# Tray2_Power_RedundantReg.net
KiCad netlist of a schematic drawn in Altium Designer
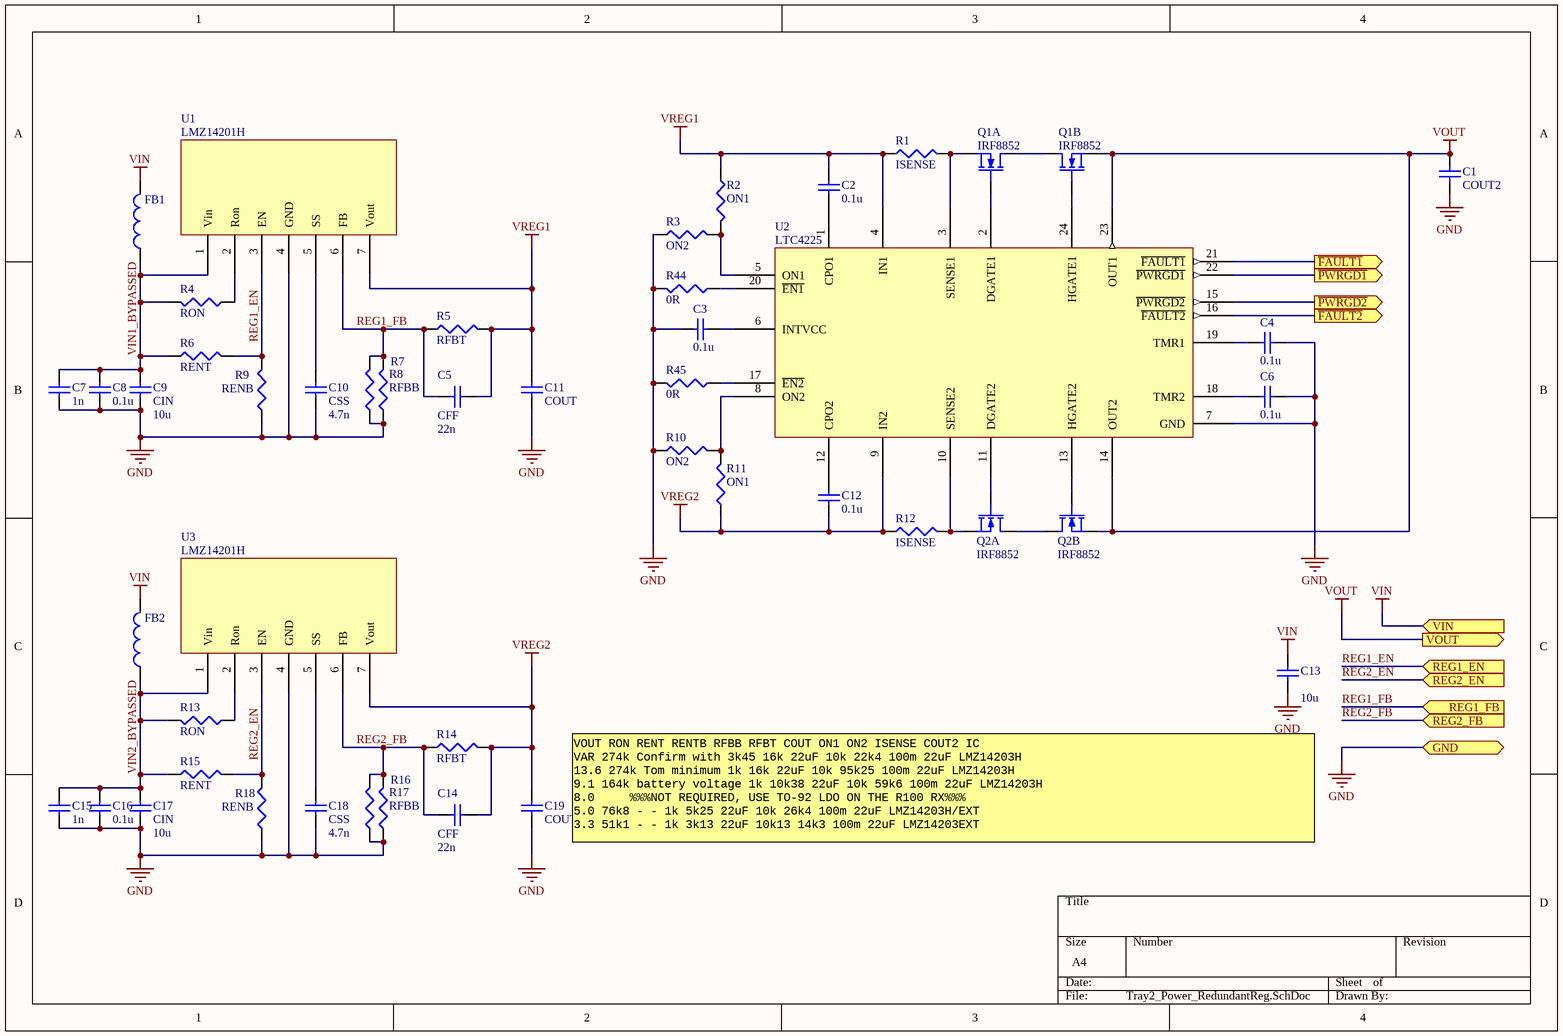
[diagram p0: Tray2_Power_RedundantReg.SchDoc]

(export (version "E")
  (design (tool "Eeschema 10.0.6"))
  (components
    (comp (ref "C1")
      (value "COUT2")
      (footprint "R1210M")
      (description "Capacitor")
      (fields (field (name "PUBLISHER") "Altium Limited"))
      (libsource (lib "Miscellaneous Devices") (part "Cap"))
    )
    (comp (ref "C2")
      (value "0.1u")
      (footprint "R0805M")
      (description "Capacitor")
      (fields (field (name "PUBLISHER") "Altium Limited"))
      (libsource (lib "Miscellaneous Devices") (part "Cap"))
    )
    (comp (ref "C3")
      (value "0.1u")
      (footprint "R0805M")
      (description "Capacitor")
      (fields (field (name "PUBLISHER") "Altium Limited"))
      (libsource (lib "Miscellaneous Devices") (part "Cap"))
    )
    (comp (ref "C4")
      (value "0.1u")
      (footprint "R0805M")
      (description "Capacitor")
      (fields (field (name "PUBLISHER") "Altium Limited"))
      (libsource (lib "Miscellaneous Devices") (part "Cap"))
    )
    (comp (ref "C5")
      (value "CFF")
      (footprint "R0805M")
      (description "Capacitor")
      (fields (field (name "ALTIUM_VALUE") "22n") (field (name "PUBLISHER") "Altium Limited"))
      (libsource (lib "Miscellaneous Devices") (part "Cap"))
    )
    (comp (ref "C6")
      (value "0.1u")
      (footprint "R0805M")
      (description "Capacitor")
      (fields (field (name "PUBLISHER") "Altium Limited"))
      (libsource (lib "Miscellaneous Devices") (part "Cap"))
    )
    (comp (ref "C7")
      (value "1n")
      (footprint "R0805M")
      (description "Capacitor")
      (fields (field (name "Comment") "CIN") (field (name "PUBLISHER") "Altium Limited"))
      (libsource (lib "Miscellaneous Devices") (part "Cap"))
    )
    (comp (ref "C8")
      (value "0.1u")
      (footprint "R0805M")
      (description "Capacitor")
      (fields (field (name "Comment") "CIN") (field (name "PUBLISHER") "Altium Limited"))
      (libsource (lib "Miscellaneous Devices") (part "Cap"))
    )
    (comp (ref "C9")
      (value "CIN")
      (footprint "R1210M")
      (description "Capacitor")
      (fields (field (name "ALTIUM_VALUE") "10u") (field (name "PUBLISHER") "Altium Limited"))
      (libsource (lib "Miscellaneous Devices") (part "Cap"))
    )
    (comp (ref "C10")
      (value "CSS")
      (footprint "R0805M")
      (description "Capacitor")
      (fields (field (name "ALTIUM_VALUE") "4.7n") (field (name "PUBLISHER") "Altium Limited"))
      (libsource (lib "Miscellaneous Devices") (part "Cap"))
    )
    (comp (ref "C11")
      (value "COUT")
      (footprint "R1210M")
      (description "Capacitor")
      (fields (field (name "PUBLISHER") "Altium Limited"))
      (libsource (lib "Miscellaneous Devices") (part "Cap"))
    )
    (comp (ref "C12")
      (value "0.1u")
      (footprint "R0805M")
      (description "Capacitor")
      (fields (field (name "PUBLISHER") "Altium Limited"))
      (libsource (lib "Miscellaneous Devices") (part "Cap"))
    )
    (comp (ref "C13")
      (value "10u")
      (footprint "R1210M")
      (description "Capacitor")
      (fields (field (name "PUBLISHER") "Altium Limited"))
      (libsource (lib "Miscellaneous Devices") (part "Cap"))
    )
    (comp (ref "C14")
      (value "CFF")
      (footprint "R0805M")
      (description "Capacitor")
      (fields (field (name "ALTIUM_VALUE") "22n") (field (name "PUBLISHER") "Altium Limited"))
      (libsource (lib "Miscellaneous Devices") (part "Cap"))
    )
    (comp (ref "C15")
      (value "1n")
      (footprint "R0805M")
      (description "Capacitor")
      (fields (field (name "Comment") "CIN") (field (name "PUBLISHER") "Altium Limited"))
      (libsource (lib "Miscellaneous Devices") (part "Cap"))
    )
    (comp (ref "C16")
      (value "0.1u")
      (footprint "R0805M")
      (description "Capacitor")
      (fields (field (name "Comment") "CIN") (field (name "PUBLISHER") "Altium Limited"))
      (libsource (lib "Miscellaneous Devices") (part "Cap"))
    )
    (comp (ref "C17")
      (value "CIN")
      (footprint "R1210M")
      (description "Capacitor")
      (fields (field (name "ALTIUM_VALUE") "10u") (field (name "PUBLISHER") "Altium Limited"))
      (libsource (lib "Miscellaneous Devices") (part "Cap"))
    )
    (comp (ref "C18")
      (value "CSS")
      (footprint "R0805M")
      (description "Capacitor")
      (fields (field (name "ALTIUM_VALUE") "4.7n") (field (name "PUBLISHER") "Altium Limited"))
      (libsource (lib "Miscellaneous Devices") (part "Cap"))
    )
    (comp (ref "C19")
      (value "COUT")
      (footprint "R1210M")
      (description "Capacitor")
      (fields (field (name "PUBLISHER") "Altium Limited"))
      (libsource (lib "Miscellaneous Devices") (part "Cap"))
    )
    (comp (ref "FB1")
      (value "~")
      (footprint "R0805M")
      (description "Inductor")
      (fields (field (name "PUBLISHER") "Altium Limited"))
      (libsource (lib "Miscellaneous Devices") (part "Inductor"))
    )
    (comp (ref "FB2")
      (value "~")
      (footprint "R0805M")
      (description "Inductor")
      (fields (field (name "PUBLISHER") "Altium Limited"))
      (libsource (lib "Miscellaneous Devices") (part "Inductor"))
    )
    (comp (ref "Q1")
      (value "IRF8852")
      (footprint "TSSOP8")
      (description "N-Channel MOSFET")
      (fields (field (name "PUBLISHER") "Altium Limited"))
      (libsource (lib "SchLib") (part "IRF8852"))
    )
    (comp (ref "Q2")
      (value "IRF8852")
      (footprint "TSSOP8")
      (description "N-Channel MOSFET")
      (fields (field (name "PUBLISHER") "Altium Limited"))
      (libsource (lib "SchLib") (part "IRF8852"))
    )
    (comp (ref "R1")
      (value "ISENSE")
      (footprint "R0805M")
      (description "Resistor")
      (fields (field (name "PUBLISHER") "Altium Limited"))
      (libsource (lib "Miscellaneous Devices") (part "Res3"))
    )
    (comp (ref "R2")
      (value "ON1")
      (footprint "R0805M")
      (description "Resistor")
      (fields (field (name "PUBLISHER") "Altium Limited"))
      (libsource (lib "Miscellaneous Devices") (part "Res3"))
    )
    (comp (ref "R3")
      (value "ON2")
      (footprint "R0805M")
      (description "Resistor")
      (fields (field (name "PUBLISHER") "Altium Limited"))
      (libsource (lib "Miscellaneous Devices") (part "Res3"))
    )
    (comp (ref "R4")
      (value "RON")
      (footprint "R0805M")
      (description "Resistor")
      (fields (field (name "PUBLISHER") "Altium Limited"))
      (libsource (lib "Miscellaneous Devices") (part "Res3"))
    )
    (comp (ref "R5")
      (value "RFBT")
      (footprint "R0805M")
      (description "Resistor")
      (fields (field (name "PUBLISHER") "Altium Limited"))
      (libsource (lib "Miscellaneous Devices") (part "Res3"))
    )
    (comp (ref "R6")
      (value "RENT")
      (footprint "R0805M")
      (description "Resistor")
      (fields (field (name "PUBLISHER") "Altium Limited"))
      (libsource (lib "Miscellaneous Devices") (part "Res3"))
    )
    (comp (ref "R7")
      (value "RFBB")
      (footprint "R0805M")
      (description "Resistor")
      (fields (field (name "PUBLISHER") "Altium Limited"))
      (libsource (lib "Miscellaneous Devices") (part "Res3"))
    )
    (comp (ref "R8")
      (value "RFBB")
      (footprint "R0805M")
      (description "Resistor")
      (fields (field (name "PUBLISHER") "Altium Limited"))
      (libsource (lib "Miscellaneous Devices") (part "Res3"))
    )
    (comp (ref "R9")
      (value "RENB")
      (footprint "R0805M")
      (description "Resistor")
      (fields (field (name "PUBLISHER") "Altium Limited"))
      (libsource (lib "Miscellaneous Devices") (part "Res3"))
    )
    (comp (ref "R10")
      (value "ON2")
      (footprint "R0805M")
      (description "Resistor")
      (fields (field (name "PUBLISHER") "Altium Limited"))
      (libsource (lib "Miscellaneous Devices") (part "Res3"))
    )
    (comp (ref "R11")
      (value "ON1")
      (footprint "R0805M")
      (description "Resistor")
      (fields (field (name "PUBLISHER") "Altium Limited"))
      (libsource (lib "Miscellaneous Devices") (part "Res3"))
    )
    (comp (ref "R12")
      (value "ISENSE")
      (footprint "R0805M")
      (description "Resistor")
      (fields (field (name "PUBLISHER") "Altium Limited"))
      (libsource (lib "Miscellaneous Devices") (part "Res3"))
    )
    (comp (ref "R13")
      (value "RON")
      (footprint "R0805M")
      (description "Resistor")
      (fields (field (name "PUBLISHER") "Altium Limited"))
      (libsource (lib "Miscellaneous Devices") (part "Res3"))
    )
    (comp (ref "R14")
      (value "RFBT")
      (footprint "R0805M")
      (description "Resistor")
      (fields (field (name "PUBLISHER") "Altium Limited"))
      (libsource (lib "Miscellaneous Devices") (part "Res3"))
    )
    (comp (ref "R15")
      (value "RENT")
      (footprint "R0805M")
      (description "Resistor")
      (fields (field (name "PUBLISHER") "Altium Limited"))
      (libsource (lib "Miscellaneous Devices") (part "Res3"))
    )
    (comp (ref "R16")
      (value "RFBB")
      (footprint "R0805M")
      (description "Resistor")
      (fields (field (name "PUBLISHER") "Altium Limited"))
      (libsource (lib "Miscellaneous Devices") (part "Res3"))
    )
    (comp (ref "R17")
      (value "RFBB")
      (footprint "R0805M")
      (description "Resistor")
      (fields (field (name "PUBLISHER") "Altium Limited"))
      (libsource (lib "Miscellaneous Devices") (part "Res3"))
    )
    (comp (ref "R18")
      (value "RENB")
      (footprint "R0805M")
      (description "Resistor")
      (fields (field (name "PUBLISHER") "Altium Limited"))
      (libsource (lib "Miscellaneous Devices") (part "Res3"))
    )
    (comp (ref "R44")
      (value "0R")
      (footprint "R0805M")
      (description "Resistor")
      (fields (field (name "PUBLISHER") "Altium Limited"))
      (libsource (lib "Miscellaneous Devices") (part "Res3"))
    )
    (comp (ref "R45")
      (value "0R")
      (footprint "R0805M")
      (description "Resistor")
      (fields (field (name "PUBLISHER") "Altium Limited"))
      (libsource (lib "Miscellaneous Devices") (part "Res3"))
    )
    (comp (ref "U1")
      (value "LMZ14201H")
      (footprint "TO-PMOD-7")
      (description "1A SIMPLE SWITCHER® Power Module for High Output  Voltage")
      (libsource (lib "SchLib") (part "LMZ14201H"))
    )
    (comp (ref "U2")
      (value "LTC4225")
      (footprint "SSOP24")
      (description "Dual Ideal Diode and  Hot Swap Controller")
      (libsource (lib "SchLib") (part "LTC4225"))
    )
    (comp (ref "U3")
      (value "LMZ14201H")
      (footprint "TO-PMOD-7")
      (description "1A SIMPLE SWITCHER® Power Module for High Output  Voltage")
      (libsource (lib "SchLib") (part "LMZ14201H"))
    )
  )
  (nets
    (net (code "1") (name "/REG1_EN") (class "Default")
      (node (ref "R6") (pin "2") (pinfunction "2_2") (pintype "passive"))
      (node (ref "R9") (pin "1") (pinfunction "1_1") (pintype "passive"))
      (node (ref "U1") (pin "3") (pinfunction "EN_3") (pintype "passive"))
    )
    (net (code "2") (name "/REG1_FB") (class "Default")
      (node (ref "C5") (pin "1") (pinfunction "1_1") (pintype "passive"))
      (node (ref "R5") (pin "1") (pinfunction "1_1") (pintype "passive"))
      (node (ref "R7") (pin "2") (pinfunction "2_2") (pintype "passive"))
      (node (ref "R8") (pin "2") (pinfunction "2_2") (pintype "passive"))
      (node (ref "U1") (pin "6") (pinfunction "FB_6") (pintype "passive"))
    )
    (net (code "3") (name "/REG2_EN") (class "Default")
      (node (ref "R15") (pin "2") (pinfunction "2_2") (pintype "passive"))
      (node (ref "R18") (pin "1") (pinfunction "1_1") (pintype "passive"))
      (node (ref "U3") (pin "3") (pinfunction "EN_3") (pintype "passive"))
    )
    (net (code "4") (name "/REG2_FB") (class "Default")
      (node (ref "C14") (pin "1") (pinfunction "1_1") (pintype "passive"))
      (node (ref "R14") (pin "1") (pinfunction "1_1") (pintype "passive"))
      (node (ref "R16") (pin "2") (pinfunction "2_2") (pintype "passive"))
      (node (ref "R17") (pin "2") (pinfunction "2_2") (pintype "passive"))
      (node (ref "U3") (pin "6") (pinfunction "FB_6") (pintype "passive"))
    )
    (net (code "5") (name "/VIN1_BYPASSED") (class "Default")
      (node (ref "C7") (pin "2") (pinfunction "2_2") (pintype "passive"))
      (node (ref "C8") (pin "2") (pinfunction "2_2") (pintype "passive"))
      (node (ref "C9") (pin "1") (pinfunction "1_1") (pintype "passive"))
      (node (ref "FB1") (pin "1") (pinfunction "1_1") (pintype "passive"))
      (node (ref "R4") (pin "2") (pinfunction "2_2") (pintype "passive"))
      (node (ref "R6") (pin "1") (pinfunction "1_1") (pintype "passive"))
      (node (ref "U1") (pin "1") (pinfunction "Vin_1") (pintype "passive"))
    )
    (net (code "6") (name "/VIN2_BYPASSED") (class "Default")
      (node (ref "C15") (pin "2") (pinfunction "2_2") (pintype "passive"))
      (node (ref "C16") (pin "2") (pinfunction "2_2") (pintype "passive"))
      (node (ref "C17") (pin "1") (pinfunction "1_1") (pintype "passive"))
      (node (ref "FB2") (pin "1") (pinfunction "1_1") (pintype "passive"))
      (node (ref "R13") (pin "2") (pinfunction "2_2") (pintype "passive"))
      (node (ref "R15") (pin "1") (pinfunction "1_1") (pintype "passive"))
      (node (ref "U3") (pin "1") (pinfunction "Vin_1") (pintype "passive"))
    )
    (net (code "7") (name "/~{FAULT1}") (class "Default")
      (node (ref "U2") (pin "21") (pinfunction "~{FAULT1}_21") (pintype "output"))
    )
    (net (code "8") (name "/~{FAULT2}") (class "Default")
      (node (ref "U2") (pin "16") (pinfunction "~{FAULT2}_16") (pintype "output"))
    )
    (net (code "9") (name "/~{PWRGD1}") (class "Default")
      (node (ref "U2") (pin "22") (pinfunction "~{PWRGD1}_22") (pintype "output"))
    )
    (net (code "10") (name "/~{PWRGD2}") (class "Default")
      (node (ref "U2") (pin "15") (pinfunction "~{PWRGD2}_15") (pintype "output"))
    )
    (net (code "11") (name "GND") (class "Default")
      (node (ref "C1") (pin "1") (pinfunction "1_1") (pintype "passive"))
      (node (ref "C10") (pin "2") (pinfunction "2_2") (pintype "passive"))
      (node (ref "C11") (pin "1") (pinfunction "1_1") (pintype "passive"))
      (node (ref "C13") (pin "2") (pinfunction "2_2") (pintype "passive"))
      (node (ref "C15") (pin "1") (pinfunction "1_1") (pintype "passive"))
      (node (ref "C16") (pin "1") (pinfunction "1_1") (pintype "passive"))
      (node (ref "C17") (pin "2") (pinfunction "2_2") (pintype "passive"))
      (node (ref "C18") (pin "2") (pinfunction "2_2") (pintype "passive"))
      (node (ref "C19") (pin "1") (pinfunction "1_1") (pintype "passive"))
      (node (ref "C3") (pin "2") (pinfunction "2_2") (pintype "passive"))
      (node (ref "C4") (pin "1") (pinfunction "1_1") (pintype "passive"))
      (node (ref "C6") (pin "1") (pinfunction "1_1") (pintype "passive"))
      (node (ref "C7") (pin "1") (pinfunction "1_1") (pintype "passive"))
      (node (ref "C8") (pin "1") (pinfunction "1_1") (pintype "passive"))
      (node (ref "C9") (pin "2") (pinfunction "2_2") (pintype "passive"))
      (node (ref "R10") (pin "1") (pinfunction "1_1") (pintype "passive"))
      (node (ref "R16") (pin "1") (pinfunction "1_1") (pintype "passive"))
      (node (ref "R17") (pin "1") (pinfunction "1_1") (pintype "passive"))
      (node (ref "R18") (pin "2") (pinfunction "2_2") (pintype "passive"))
      (node (ref "R3") (pin "1") (pinfunction "1_1") (pintype "passive"))
      (node (ref "R44") (pin "2") (pinfunction "2_2") (pintype "passive"))
      (node (ref "R45") (pin "2") (pinfunction "2_2") (pintype "passive"))
      (node (ref "R7") (pin "1") (pinfunction "1_1") (pintype "passive"))
      (node (ref "R8") (pin "1") (pinfunction "1_1") (pintype "passive"))
      (node (ref "R9") (pin "2") (pinfunction "2_2") (pintype "passive"))
      (node (ref "U1") (pin "4") (pinfunction "GND_4") (pintype "passive"))
      (node (ref "U2") (pin "7") (pinfunction "GND_7") (pintype "passive"))
      (node (ref "U3") (pin "4") (pinfunction "GND_4") (pintype "passive"))
    )
    (net (code "12") (name "Net-(Q1A-D)") (class "Default")
      (node (ref "Q1") (pin "D1") (pinfunction "D_D1") (pintype "passive"))
      (node (ref "Q1") (pin "D2") (pinfunction "D_D2") (pintype "passive"))
    )
    (net (code "13") (name "Net-(Q1A-G)") (class "Default")
      (node (ref "Q1") (pin "G1") (pinfunction "G_G1") (pintype "passive"))
      (node (ref "U2") (pin "2") (pinfunction "DGATE1_2") (pintype "passive"))
    )
    (net (code "14") (name "Net-(Q1A-S)") (class "Default")
      (node (ref "Q1") (pin "S1") (pinfunction "S_S1") (pintype "passive"))
      (node (ref "R1") (pin "2") (pinfunction "2_2") (pintype "passive"))
      (node (ref "U2") (pin "3") (pinfunction "SENSE1_3") (pintype "passive"))
    )
    (net (code "15") (name "Net-(Q1B-G)") (class "Default")
      (node (ref "Q1") (pin "G2") (pinfunction "G_G2") (pintype "passive"))
      (node (ref "U2") (pin "24") (pinfunction "HGATE1_24") (pintype "passive"))
    )
    (net (code "16") (name "Net-(Q2A-D)") (class "Default")
      (node (ref "Q2") (pin "D1") (pinfunction "D_D1") (pintype "passive"))
      (node (ref "Q2") (pin "D2") (pinfunction "D_D2") (pintype "passive"))
    )
    (net (code "17") (name "Net-(Q2A-G)") (class "Default")
      (node (ref "Q2") (pin "G1") (pinfunction "G_G1") (pintype "passive"))
      (node (ref "U2") (pin "11") (pinfunction "DGATE2_11") (pintype "passive"))
    )
    (net (code "18") (name "Net-(Q2A-S)") (class "Default")
      (node (ref "Q2") (pin "S1") (pinfunction "S_S1") (pintype "passive"))
      (node (ref "R12") (pin "2") (pinfunction "2_2") (pintype "passive"))
      (node (ref "U2") (pin "10") (pinfunction "SENSE2_10") (pintype "passive"))
    )
    (net (code "19") (name "Net-(Q2B-G)") (class "Default")
      (node (ref "Q2") (pin "G2") (pinfunction "G_G2") (pintype "passive"))
      (node (ref "U2") (pin "13") (pinfunction "HGATE2_13") (pintype "passive"))
    )
    (net (code "20") (name "Net-(U1-Ron)") (class "Default")
      (node (ref "R4") (pin "1") (pinfunction "1_1") (pintype "passive"))
      (node (ref "U1") (pin "2") (pinfunction "Ron_2") (pintype "passive"))
    )
    (net (code "21") (name "Net-(U1-SS)") (class "Default")
      (node (ref "C10") (pin "1") (pinfunction "1_1") (pintype "passive"))
      (node (ref "U1") (pin "5") (pinfunction "SS_5") (pintype "passive"))
    )
    (net (code "22") (name "Net-(U2-CPO1)") (class "Default")
      (node (ref "C2") (pin "2") (pinfunction "2_2") (pintype "passive"))
      (node (ref "U2") (pin "1") (pinfunction "CPO1_1") (pintype "passive"))
    )
    (net (code "23") (name "Net-(U2-CPO2)") (class "Default")
      (node (ref "C12") (pin "1") (pinfunction "1_1") (pintype "passive"))
      (node (ref "U2") (pin "12") (pinfunction "CPO2_12") (pintype "passive"))
    )
    (net (code "24") (name "Net-(U2-INTVCC)") (class "Default")
      (node (ref "C3") (pin "1") (pinfunction "1_1") (pintype "passive"))
      (node (ref "U2") (pin "6") (pinfunction "INTVCC_6") (pintype "passive"))
    )
    (net (code "25") (name "Net-(U2-ON1)") (class "Default")
      (node (ref "R2") (pin "2") (pinfunction "2_2") (pintype "passive"))
      (node (ref "R3") (pin "2") (pinfunction "2_2") (pintype "passive"))
      (node (ref "U2") (pin "5") (pinfunction "ON1_5") (pintype "passive"))
    )
    (net (code "26") (name "Net-(U2-ON2)") (class "Default")
      (node (ref "R10") (pin "2") (pinfunction "2_2") (pintype "passive"))
      (node (ref "R11") (pin "2") (pinfunction "2_2") (pintype "passive"))
      (node (ref "U2") (pin "8") (pinfunction "ON2_8") (pintype "passive"))
    )
    (net (code "27") (name "Net-(U2-TMR1)") (class "Default")
      (node (ref "C4") (pin "2") (pinfunction "2_2") (pintype "passive"))
      (node (ref "U2") (pin "19") (pinfunction "TMR1_19") (pintype "passive"))
    )
    (net (code "28") (name "Net-(U2-TMR2)") (class "Default")
      (node (ref "C6") (pin "2") (pinfunction "2_2") (pintype "passive"))
      (node (ref "U2") (pin "18") (pinfunction "TMR2_18") (pintype "passive"))
    )
    (net (code "29") (name "Net-(U2-~{EN1})") (class "Default")
      (node (ref "R44") (pin "1") (pinfunction "1_1") (pintype "passive"))
      (node (ref "U2") (pin "20") (pinfunction "~{EN1}_20") (pintype "passive"))
    )
    (net (code "30") (name "Net-(U2-~{EN2})") (class "Default")
      (node (ref "R45") (pin "1") (pinfunction "1_1") (pintype "passive"))
      (node (ref "U2") (pin "17") (pinfunction "~{EN2}_17") (pintype "passive"))
    )
    (net (code "31") (name "Net-(U3-Ron)") (class "Default")
      (node (ref "R13") (pin "1") (pinfunction "1_1") (pintype "passive"))
      (node (ref "U3") (pin "2") (pinfunction "Ron_2") (pintype "passive"))
    )
    (net (code "32") (name "Net-(U3-SS)") (class "Default")
      (node (ref "C18") (pin "1") (pinfunction "1_1") (pintype "passive"))
      (node (ref "U3") (pin "5") (pinfunction "SS_5") (pintype "passive"))
    )
    (net (code "33") (name "VIN") (class "Default")
      (node (ref "C13") (pin "1") (pinfunction "1_1") (pintype "passive"))
      (node (ref "FB1") (pin "2") (pinfunction "2_2") (pintype "passive"))
      (node (ref "FB2") (pin "2") (pinfunction "2_2") (pintype "passive"))
    )
    (net (code "34") (name "VOUT") (class "Default")
      (node (ref "C1") (pin "2") (pinfunction "2_2") (pintype "passive"))
      (node (ref "Q1") (pin "S2") (pinfunction "S_S2") (pintype "passive"))
      (node (ref "Q2") (pin "S2") (pinfunction "S_S2") (pintype "passive"))
      (node (ref "U2") (pin "14") (pinfunction "OUT2_14") (pintype "passive"))
      (node (ref "U2") (pin "23") (pinfunction "OUT1_23") (pintype "output"))
    )
    (net (code "35") (name "VREG1") (class "Default")
      (node (ref "C11") (pin "2") (pinfunction "2_2") (pintype "passive"))
      (node (ref "C2") (pin "1") (pinfunction "1_1") (pintype "passive"))
      (node (ref "C5") (pin "2") (pinfunction "2_2") (pintype "passive"))
      (node (ref "R1") (pin "1") (pinfunction "1_1") (pintype "passive"))
      (node (ref "R2") (pin "1") (pinfunction "1_1") (pintype "passive"))
      (node (ref "R5") (pin "2") (pinfunction "2_2") (pintype "passive"))
      (node (ref "U1") (pin "7") (pinfunction "Vout_7") (pintype "passive"))
      (node (ref "U2") (pin "4") (pinfunction "IN1_4") (pintype "passive"))
    )
    (net (code "36") (name "VREG2") (class "Default")
      (node (ref "C12") (pin "2") (pinfunction "2_2") (pintype "passive"))
      (node (ref "C14") (pin "2") (pinfunction "2_2") (pintype "passive"))
      (node (ref "C19") (pin "2") (pinfunction "2_2") (pintype "passive"))
      (node (ref "R11") (pin "1") (pinfunction "1_1") (pintype "passive"))
      (node (ref "R12") (pin "1") (pinfunction "1_1") (pintype "passive"))
      (node (ref "R14") (pin "2") (pinfunction "2_2") (pintype "passive"))
      (node (ref "U2") (pin "9") (pinfunction "IN2_9") (pintype "passive"))
      (node (ref "U3") (pin "7") (pinfunction "Vout_7") (pintype "passive"))
    )
  )
)
